# pth_supply_servos_molex.net
KiCad netlist of a schematic drawn in EAGLE
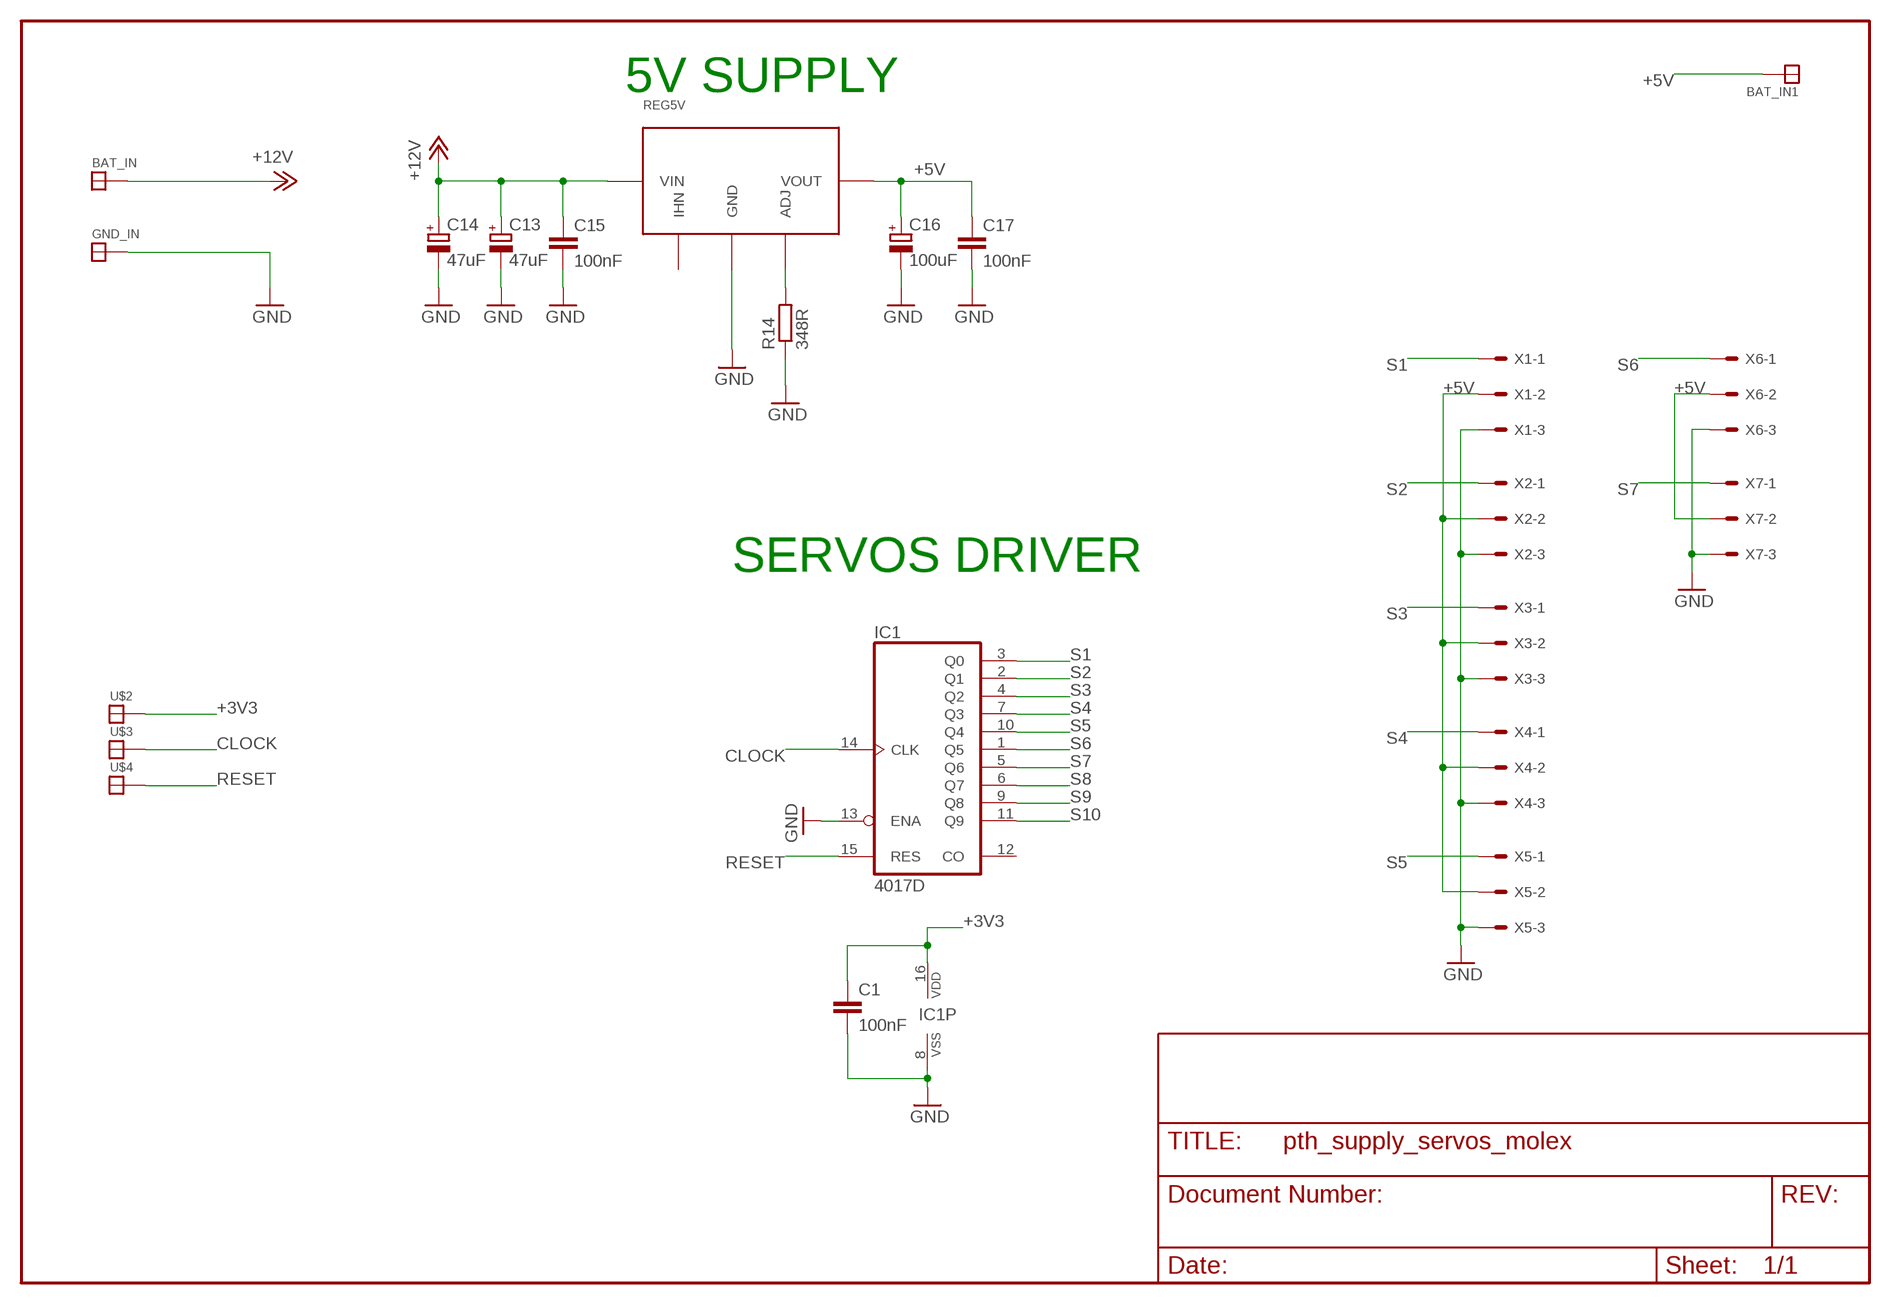
[diagram p0: schematic, sheet 1]

(export (version "E")
  (design (tool "Eeschema 10.0.6"))
  (components
    (comp (ref "BAT_IN")
      (value "SOLDER_PAD150_75")
      (footprint "eagle-import:SOLD_PAD_150_75")
      (libsource (lib "eagle-import") (part "SOLDER_PAD150_75"))
    )
    (comp (ref "BAT_IN1")
      (value "SOLDER_PAD150_75")
      (footprint "eagle-import:SOLD_PAD_150_75")
      (libsource (lib "eagle-import") (part "SOLDER_PAD150_75"))
    )
    (comp (ref "C1")
      (value "100nF")
      (footprint "eagle-import:C0805K")
      (libsource (lib "eagle-import") (part "C-EUC0805K"))
    )
    (comp (ref "C13")
      (value "47uF")
      (footprint "eagle-import:SMC_D")
      (libsource (lib "eagle-import") (part "CPOL-EUSMCD"))
    )
    (comp (ref "C14")
      (value "47uF")
      (footprint "eagle-import:SMC_D")
      (libsource (lib "eagle-import") (part "CPOL-EUSMCD"))
    )
    (comp (ref "C15")
      (value "100nF")
      (footprint "eagle-import:C0805K")
      (libsource (lib "eagle-import") (part "C-EUC0805K"))
    )
    (comp (ref "C16")
      (value "100uF")
      (footprint "eagle-import:SMC_D")
      (libsource (lib "eagle-import") (part "CPOL-EUSMCD"))
    )
    (comp (ref "C17")
      (value "100nF")
      (footprint "eagle-import:C0805K")
      (libsource (lib "eagle-import") (part "C-EUC0805K"))
    )
    (comp (ref "GND_IN")
      (value "SOLDER_PAD150_75")
      (footprint "eagle-import:SOLD_PAD_150_75")
      (libsource (lib "eagle-import") (part "SOLDER_PAD150_75"))
    )
    (comp (ref "IC1")
      (value "4017D")
      (footprint "eagle-import:SO16")
      (libsource (lib "eagle-import") (part "4017D"))
    )
    (comp (ref "R14")
      (value "348R")
      (footprint "eagle-import:R0805")
      (libsource (lib "eagle-import") (part "R-EU_R0805"))
    )
    (comp (ref "REG5V")
      (value "PTH")
      (footprint "eagle-import:PTH")
      (libsource (lib "eagle-import") (part "PTH"))
    )
    (comp (ref "U$2")
      (value "SOLDER_PAD100_50")
      (footprint "eagle-import:SOLDER_PAD_100_50")
      (libsource (lib "eagle-import") (part "SOLDER_PAD100_50"))
    )
    (comp (ref "U$3")
      (value "SOLDER_PAD100_50")
      (footprint "eagle-import:SOLDER_PAD_100_50")
      (libsource (lib "eagle-import") (part "SOLDER_PAD100_50"))
    )
    (comp (ref "U$4")
      (value "SOLDER_PAD100_50")
      (footprint "eagle-import:SOLDER_PAD_100_50")
      (libsource (lib "eagle-import") (part "SOLDER_PAD100_50"))
    )
    (comp (ref "X1")
      (value "53047-03")
      (footprint "eagle-import:53047-03")
      (libsource (lib "eagle-import") (part "53?-03047"))
    )
    (comp (ref "X2")
      (value "53047-03")
      (footprint "eagle-import:53047-03")
      (libsource (lib "eagle-import") (part "53?-03047"))
    )
    (comp (ref "X3")
      (value "53047-03")
      (footprint "eagle-import:53047-03")
      (libsource (lib "eagle-import") (part "53?-03047"))
    )
    (comp (ref "X4")
      (value "53047-03")
      (footprint "eagle-import:53047-03")
      (libsource (lib "eagle-import") (part "53?-03047"))
    )
    (comp (ref "X5")
      (value "53047-03")
      (footprint "eagle-import:53047-03")
      (libsource (lib "eagle-import") (part "53?-03047"))
    )
    (comp (ref "X6")
      (value "53047-03")
      (footprint "eagle-import:53047-03")
      (libsource (lib "eagle-import") (part "53?-03047"))
    )
    (comp (ref "X7")
      (value "53047-03")
      (footprint "eagle-import:53047-03")
      (libsource (lib "eagle-import") (part "53?-03047"))
    )
  )
  (nets
    (net (code "1") (name "+12V") (class "Default")
      (node (ref "BAT_IN") (pin "P$1") (pinfunction "P$1_P$1") (pintype "bidirectional"))
      (node (ref "C13") (pin "+") (pinfunction "+_+") (pintype "passive"))
      (node (ref "C14") (pin "+") (pinfunction "+_+") (pintype "passive"))
      (node (ref "C15") (pin "1") (pinfunction "1_1") (pintype "passive"))
      (node (ref "REG5V") (pin "P$1") (pinfunction "VIN_P$1") (pintype "bidirectional"))
    )
    (net (code "2") (name "/+3V3") (class "Default")
      (node (ref "C1") (pin "1") (pinfunction "1_1") (pintype "passive"))
      (node (ref "IC1") (pin "16") (pinfunction "VDD_16") (pintype "power_in"))
      (node (ref "U$2") (pin "P$1") (pinfunction "P$1_P$1") (pintype "bidirectional"))
    )
    (net (code "3") (name "/+5V") (class "Default")
      (node (ref "BAT_IN1") (pin "P$1") (pinfunction "P$1_P$1") (pintype "bidirectional"))
      (node (ref "C16") (pin "+") (pinfunction "+_+") (pintype "passive"))
      (node (ref "C17") (pin "1") (pinfunction "1_1") (pintype "passive"))
      (node (ref "REG5V") (pin "P$3") (pinfunction "VOUT_P$3") (pintype "bidirectional"))
      (node (ref "X1") (pin "2") (pinfunction "S_2") (pintype "passive"))
      (node (ref "X2") (pin "2") (pinfunction "S_2") (pintype "passive"))
      (node (ref "X3") (pin "2") (pinfunction "S_2") (pintype "passive"))
      (node (ref "X4") (pin "2") (pinfunction "S_2") (pintype "passive"))
      (node (ref "X5") (pin "2") (pinfunction "S_2") (pintype "passive"))
      (node (ref "X6") (pin "2") (pinfunction "S_2") (pintype "passive"))
      (node (ref "X7") (pin "2") (pinfunction "S_2") (pintype "passive"))
    )
    (net (code "4") (name "/CLOCK") (class "Default")
      (node (ref "IC1") (pin "14") (pinfunction "CLK_14") (pintype "input"))
      (node (ref "U$3") (pin "P$1") (pinfunction "P$1_P$1") (pintype "bidirectional"))
    )
    (net (code "5") (name "/RESET") (class "Default")
      (node (ref "IC1") (pin "15") (pinfunction "RES_15") (pintype "input"))
      (node (ref "U$4") (pin "P$1") (pinfunction "P$1_P$1") (pintype "bidirectional"))
    )
    (net (code "6") (name "/S1") (class "Default")
      (node (ref "IC1") (pin "3") (pinfunction "Q0_3") (pintype "output"))
      (node (ref "X1") (pin "1") (pinfunction "S_1") (pintype "passive"))
    )
    (net (code "7") (name "/S2") (class "Default")
      (node (ref "IC1") (pin "2") (pinfunction "Q1_2") (pintype "output"))
      (node (ref "X2") (pin "1") (pinfunction "S_1") (pintype "passive"))
    )
    (net (code "8") (name "/S3") (class "Default")
      (node (ref "IC1") (pin "4") (pinfunction "Q2_4") (pintype "output"))
      (node (ref "X3") (pin "1") (pinfunction "S_1") (pintype "passive"))
    )
    (net (code "9") (name "/S4") (class "Default")
      (node (ref "IC1") (pin "7") (pinfunction "Q3_7") (pintype "output"))
      (node (ref "X4") (pin "1") (pinfunction "S_1") (pintype "passive"))
    )
    (net (code "10") (name "/S5") (class "Default")
      (node (ref "IC1") (pin "10") (pinfunction "Q4_10") (pintype "output"))
      (node (ref "X5") (pin "1") (pinfunction "S_1") (pintype "passive"))
    )
    (net (code "11") (name "/S6") (class "Default")
      (node (ref "IC1") (pin "1") (pinfunction "Q5_1") (pintype "output"))
      (node (ref "X6") (pin "1") (pinfunction "S_1") (pintype "passive"))
    )
    (net (code "12") (name "/S7") (class "Default")
      (node (ref "IC1") (pin "5") (pinfunction "Q6_5") (pintype "output"))
      (node (ref "X7") (pin "1") (pinfunction "S_1") (pintype "passive"))
    )
    (net (code "13") (name "/S8") (class "Default")
      (node (ref "IC1") (pin "6") (pinfunction "Q7_6") (pintype "output"))
    )
    (net (code "14") (name "/S9") (class "Default")
      (node (ref "IC1") (pin "9") (pinfunction "Q8_9") (pintype "output"))
    )
    (net (code "15") (name "/S10") (class "Default")
      (node (ref "IC1") (pin "11") (pinfunction "Q9_11") (pintype "output"))
    )
    (net (code "16") (name "GND") (class "Default")
      (node (ref "C1") (pin "2") (pinfunction "2_2") (pintype "passive"))
      (node (ref "C13") (pin "-") (pinfunction "-_-") (pintype "passive"))
      (node (ref "C14") (pin "-") (pinfunction "-_-") (pintype "passive"))
      (node (ref "C15") (pin "2") (pinfunction "2_2") (pintype "passive"))
      (node (ref "C16") (pin "-") (pinfunction "-_-") (pintype "passive"))
      (node (ref "C17") (pin "2") (pinfunction "2_2") (pintype "passive"))
      (node (ref "GND_IN") (pin "P$1") (pinfunction "P$1_P$1") (pintype "bidirectional"))
      (node (ref "IC1") (pin "13") (pinfunction "ENA_13") (pintype "input"))
      (node (ref "IC1") (pin "8") (pinfunction "VSS_8") (pintype "power_in"))
      (node (ref "R14") (pin "1") (pinfunction "1_1") (pintype "passive"))
      (node (ref "REG5V") (pin "P$2") (pinfunction "GND_P$2") (pintype "bidirectional"))
      (node (ref "X1") (pin "3") (pinfunction "S_3") (pintype "passive"))
      (node (ref "X2") (pin "3") (pinfunction "S_3") (pintype "passive"))
      (node (ref "X3") (pin "3") (pinfunction "S_3") (pintype "passive"))
      (node (ref "X4") (pin "3") (pinfunction "S_3") (pintype "passive"))
      (node (ref "X5") (pin "3") (pinfunction "S_3") (pintype "passive"))
      (node (ref "X6") (pin "3") (pinfunction "S_3") (pintype "passive"))
      (node (ref "X7") (pin "3") (pinfunction "S_3") (pintype "passive"))
    )
    (net (code "17") (name "Net-(REG5V-ADJ)") (class "Default")
      (node (ref "R14") (pin "2") (pinfunction "2_2") (pintype "passive"))
      (node (ref "REG5V") (pin "P$4") (pinfunction "ADJ_P$4") (pintype "bidirectional"))
    )
    (net (code "18") (name "unconnected-(IC1A-CO-Pad12)") (class "Default")
      (node (ref "IC1") (pin "12") (pinfunction "CO_12") (pintype "output"))
    )
    (net (code "19") (name "unconnected-(REG5V-IHN-PadP$5)") (class "Default")
      (node (ref "REG5V") (pin "P$5") (pinfunction "IHN_P$5") (pintype "bidirectional"))
    )
  )
)
